# MeasureMent.net
KiCad netlist of a schematic drawn in Altium Designer
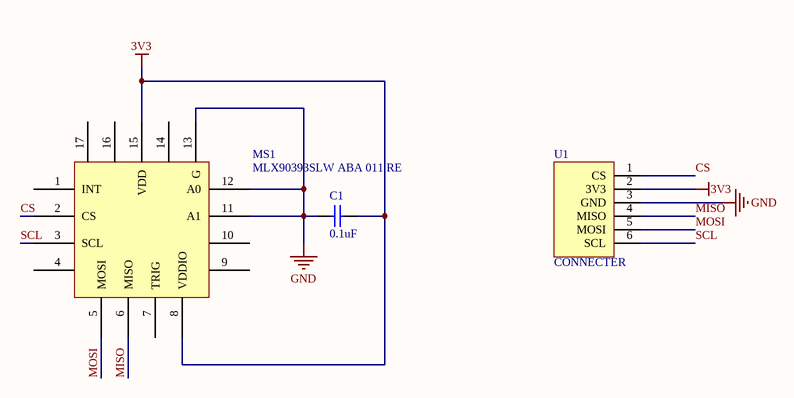
[diagram p0: MeasureMent.SchDoc]

(export (version "E")
  (design (tool "Eeschema 10.0.6"))
  (components
    (comp (ref "C1")
      (value "0.1uF")
      (footprint "0603_C")
      (description "capacitance")
      (libsource (lib "Mlx90393") (part "CAP_0.1uF"))
    )
    (comp (ref "MS1")
      (value "MLX90393SLW ABA 011 RE")
      (footprint "VQFN-16_EP_3.0x3.0xo.5P")
      (description "sensor")
      (libsource (lib "magjoint_MCU") (part "MLX90393SLW ABA 011 RE"))
    )
    (comp (ref "U1")
      (value "CONNECTER")
      (footprint "CONNECTOR")
      (libsource (lib "Mlx90393") (part "CONNECTER"))
    )
  )
  (nets
    (net (code "1") (name "/CS") (class "Default")
      (node (ref "MS1") (pin "2") (pinfunction "CS_2") (pintype "passive"))
      (node (ref "U1") (pin "1") (pinfunction "CS_1") (pintype "passive"))
    )
    (net (code "2") (name "/MISO") (class "Default")
      (node (ref "MS1") (pin "6") (pinfunction "MISO_6") (pintype "passive"))
      (node (ref "U1") (pin "4") (pinfunction "MISO_4") (pintype "passive"))
    )
    (net (code "3") (name "/MOSI") (class "Default")
      (node (ref "MS1") (pin "5") (pinfunction "MOSI_5") (pintype "passive"))
      (node (ref "U1") (pin "5") (pinfunction "MOSI_5") (pintype "passive"))
    )
    (net (code "4") (name "/SCL") (class "Default")
      (node (ref "MS1") (pin "3") (pinfunction "SCL_3") (pintype "passive"))
      (node (ref "U1") (pin "6") (pinfunction "SCL_6") (pintype "passive"))
    )
    (net (code "5") (name "3V3") (class "Default")
      (node (ref "C1") (pin "2") (pinfunction "2_2") (pintype "passive"))
      (node (ref "MS1") (pin "15") (pinfunction "VDD_15") (pintype "passive"))
      (node (ref "MS1") (pin "8") (pinfunction "VDDIO_8") (pintype "passive"))
      (node (ref "U1") (pin "2") (pinfunction "3V3_2") (pintype "passive"))
    )
    (net (code "6") (name "GND") (class "Default")
      (node (ref "C1") (pin "1") (pinfunction "1_1") (pintype "passive"))
      (node (ref "MS1") (pin "11") (pinfunction "A1_11") (pintype "passive"))
      (node (ref "MS1") (pin "12") (pinfunction "A0_12") (pintype "passive"))
      (node (ref "MS1") (pin "13") (pinfunction "G_13") (pintype "passive"))
      (node (ref "U1") (pin "3") (pinfunction "GND_3") (pintype "passive"))
    )
    (net (code "7") (name "unconnected-(MS1-INT-Pad1)") (class "Default")
      (node (ref "MS1") (pin "1") (pinfunction "INT_1") (pintype "passive"))
    )
    (net (code "8") (name "unconnected-(MS1-Pad4)") (class "Default")
      (node (ref "MS1") (pin "4") (pintype "passive"))
    )
    (net (code "9") (name "unconnected-(MS1-Pad9)") (class "Default")
      (node (ref "MS1") (pin "9") (pintype "passive"))
    )
    (net (code "10") (name "unconnected-(MS1-Pad10)") (class "Default")
      (node (ref "MS1") (pin "10") (pintype "passive"))
    )
    (net (code "11") (name "unconnected-(MS1-Pad14)") (class "Default")
      (node (ref "MS1") (pin "14") (pintype "passive"))
    )
    (net (code "12") (name "unconnected-(MS1-Pad16)") (class "Default")
      (node (ref "MS1") (pin "16") (pintype "passive"))
    )
    (net (code "13") (name "unconnected-(MS1-Pad17)") (class "Default")
      (node (ref "MS1") (pin "17") (pintype "passive"))
    )
    (net (code "14") (name "unconnected-(MS1-TRIG-Pad7)") (class "Default")
      (node (ref "MS1") (pin "7") (pinfunction "TRIG_7") (pintype "passive"))
    )
  )
)
